# MyFly2.net
KiCad netlist of a schematic drawn in Altium Designer
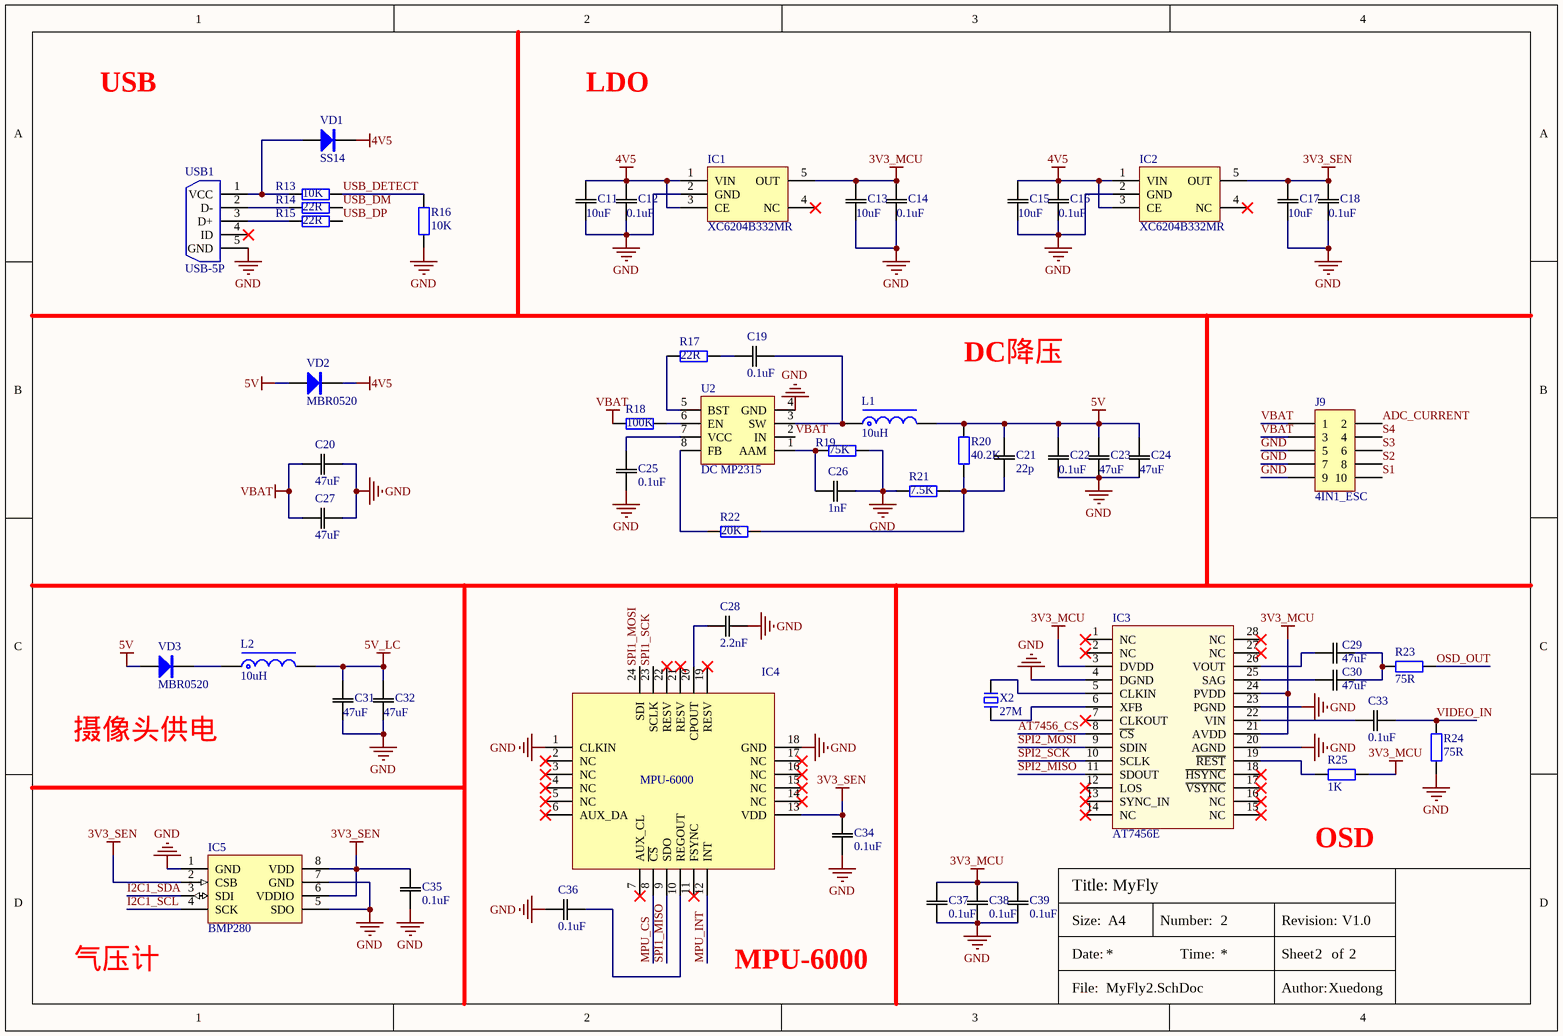
[diagram p0: MyFly2.SchDoc]

(export (version "E")
  (design (tool "Eeschema 10.0.6"))
  (components
    (comp (ref "C11")
      (value "10uF")
      (footprint "CAP_0603")
      (description "无极性贴片电容")
      (fields
        (field (name "MANUFACTURER_PART_NUMBER") "04023A0R3BAT2A")
        (field (name "COPYRIGHT") "Copyright (C) 2016 Accelerated Designs. All rights reserved")
      )
      (libsource (lib "mySchLib") (part "CAP"))
    )
    (comp (ref "C12")
      (value "0.1uF")
      (footprint "CAP_0603")
      (description "无极性贴片电容")
      (fields
        (field (name "MANUFACTURER_PART_NUMBER") "04023A0R3BAT2A")
        (field (name "COPYRIGHT") "Copyright (C) 2016 Accelerated Designs. All rights reserved")
      )
      (libsource (lib "mySchLib") (part "CAP"))
    )
    (comp (ref "C13")
      (value "10uF")
      (footprint "CAP_0603")
      (description "无极性贴片电容")
      (fields
        (field (name "MANUFACTURER_PART_NUMBER") "04023A0R3BAT2A")
        (field (name "COPYRIGHT") "Copyright (C) 2016 Accelerated Designs. All rights reserved")
      )
      (libsource (lib "mySchLib") (part "CAP"))
    )
    (comp (ref "C14")
      (value "0.1uF")
      (footprint "CAP_0603")
      (description "无极性贴片电容")
      (fields
        (field (name "MANUFACTURER_PART_NUMBER") "04023A0R3BAT2A")
        (field (name "COPYRIGHT") "Copyright (C) 2016 Accelerated Designs. All rights reserved")
      )
      (libsource (lib "mySchLib") (part "CAP"))
    )
    (comp (ref "C15")
      (value "10uF")
      (footprint "CAP_0603")
      (description "无极性贴片电容")
      (fields
        (field (name "MANUFACTURER_PART_NUMBER") "04023A0R3BAT2A")
        (field (name "COPYRIGHT") "Copyright (C) 2016 Accelerated Designs. All rights reserved")
      )
      (libsource (lib "mySchLib") (part "CAP"))
    )
    (comp (ref "C16")
      (value "0.1uF")
      (footprint "CAP_0603")
      (description "无极性贴片电容")
      (fields
        (field (name "MANUFACTURER_PART_NUMBER") "04023A0R3BAT2A")
        (field (name "COPYRIGHT") "Copyright (C) 2016 Accelerated Designs. All rights reserved")
      )
      (libsource (lib "mySchLib") (part "CAP"))
    )
    (comp (ref "C17")
      (value "10uF")
      (footprint "CAP_0603")
      (description "无极性贴片电容")
      (fields
        (field (name "MANUFACTURER_PART_NUMBER") "04023A0R3BAT2A")
        (field (name "COPYRIGHT") "Copyright (C) 2016 Accelerated Designs. All rights reserved")
      )
      (libsource (lib "mySchLib") (part "CAP"))
    )
    (comp (ref "C18")
      (value "0.1uF")
      (footprint "CAP_0603")
      (description "无极性贴片电容")
      (fields
        (field (name "MANUFACTURER_PART_NUMBER") "04023A0R3BAT2A")
        (field (name "COPYRIGHT") "Copyright (C) 2016 Accelerated Designs. All rights reserved")
      )
      (libsource (lib "mySchLib") (part "CAP"))
    )
    (comp (ref "C19")
      (value "0.1uF")
      (footprint "CAP_0603")
      (description "无极性贴片电容")
      (fields
        (field (name "MANUFACTURER_PART_NUMBER") "04023A0R3BAT2A")
        (field (name "COPYRIGHT") "Copyright (C) 2016 Accelerated Designs. All rights reserved")
      )
      (libsource (lib "mySchLib") (part "CAP"))
    )
    (comp (ref "C20")
      (value "47uF")
      (footprint "CAP_1206")
      (description "无极性贴片电容")
      (fields
        (field (name "MANUFACTURER_PART_NUMBER") "04023A0R3BAT2A")
        (field (name "COPYRIGHT") "Copyright (C) 2016 Accelerated Designs. All rights reserved")
      )
      (libsource (lib "mySchLib") (part "CAP"))
    )
    (comp (ref "C21")
      (value "22p")
      (footprint "CAP_0603")
      (description "无极性贴片电容")
      (fields
        (field (name "MANUFACTURER_PART_NUMBER") "04023A0R3BAT2A")
        (field (name "COPYRIGHT") "Copyright (C) 2016 Accelerated Designs. All rights reserved")
      )
      (libsource (lib "mySchLib") (part "CAP"))
    )
    (comp (ref "C22")
      (value "0.1uF")
      (footprint "CAP_0603")
      (description "无极性贴片电容")
      (fields
        (field (name "MANUFACTURER_PART_NUMBER") "04023A0R3BAT2A")
        (field (name "COPYRIGHT") "Copyright (C) 2016 Accelerated Designs. All rights reserved")
      )
      (libsource (lib "mySchLib") (part "CAP"))
    )
    (comp (ref "C23")
      (value "47uF")
      (footprint "CAP_1206")
      (description "无极性贴片电容")
      (fields
        (field (name "MANUFACTURER_PART_NUMBER") "04023A0R3BAT2A")
        (field (name "COPYRIGHT") "Copyright (C) 2016 Accelerated Designs. All rights reserved")
      )
      (libsource (lib "mySchLib") (part "CAP"))
    )
    (comp (ref "C24")
      (value "47uF")
      (footprint "CAP_1206")
      (description "无极性贴片电容")
      (fields
        (field (name "MANUFACTURER_PART_NUMBER") "04023A0R3BAT2A")
        (field (name "COPYRIGHT") "Copyright (C) 2016 Accelerated Designs. All rights reserved")
      )
      (libsource (lib "mySchLib") (part "CAP"))
    )
    (comp (ref "C25")
      (value "0.1uF")
      (footprint "CAP_0603")
      (description "无极性贴片电容")
      (fields
        (field (name "MANUFACTURER_PART_NUMBER") "04023A0R3BAT2A")
        (field (name "COPYRIGHT") "Copyright (C) 2016 Accelerated Designs. All rights reserved")
      )
      (libsource (lib "mySchLib") (part "CAP"))
    )
    (comp (ref "C26")
      (value "1nF")
      (footprint "CAP_0603")
      (description "无极性贴片电容")
      (fields
        (field (name "MANUFACTURER_PART_NUMBER") "04023A0R3BAT2A")
        (field (name "COPYRIGHT") "Copyright (C) 2016 Accelerated Designs. All rights reserved")
      )
      (libsource (lib "mySchLib") (part "CAP"))
    )
    (comp (ref "C27")
      (value "47uF")
      (footprint "CAP_1206")
      (description "无极性贴片电容")
      (fields
        (field (name "MANUFACTURER_PART_NUMBER") "04023A0R3BAT2A")
        (field (name "COPYRIGHT") "Copyright (C) 2016 Accelerated Designs. All rights reserved")
      )
      (libsource (lib "mySchLib") (part "CAP"))
    )
    (comp (ref "C28")
      (value "2.2nF")
      (footprint "CAP_0402")
      (description "无极性贴片电容")
      (fields
        (field (name "MANUFACTURER_PART_NUMBER") "04023A0R3BAT2A")
        (field (name "COPYRIGHT") "Copyright (C) 2016 Accelerated Designs. All rights reserved")
      )
      (libsource (lib "mySchLib") (part "CAP"))
    )
    (comp (ref "C29")
      (value "47uF")
      (footprint "CAP_0805")
      (description "无极性贴片电容")
      (fields
        (field (name "MANUFACTURER_PART_NUMBER") "04023A0R3BAT2A")
        (field (name "COPYRIGHT") "Copyright (C) 2016 Accelerated Designs. All rights reserved")
      )
      (libsource (lib "mySchLib") (part "CAP"))
    )
    (comp (ref "C30")
      (value "47uF")
      (footprint "CAP_0805")
      (description "无极性贴片电容")
      (fields
        (field (name "MANUFACTURER_PART_NUMBER") "04023A0R3BAT2A")
        (field (name "COPYRIGHT") "Copyright (C) 2016 Accelerated Designs. All rights reserved")
      )
      (libsource (lib "mySchLib") (part "CAP"))
    )
    (comp (ref "C31")
      (value "47uF")
      (footprint "CAP_0805")
      (description "无极性贴片电容")
      (fields
        (field (name "MANUFACTURER_PART_NUMBER") "04023A0R3BAT2A")
        (field (name "COPYRIGHT") "Copyright (C) 2016 Accelerated Designs. All rights reserved")
      )
      (libsource (lib "mySchLib") (part "CAP"))
    )
    (comp (ref "C32")
      (value "47uF")
      (footprint "CAP_0805")
      (description "无极性贴片电容")
      (fields
        (field (name "MANUFACTURER_PART_NUMBER") "04023A0R3BAT2A")
        (field (name "COPYRIGHT") "Copyright (C) 2016 Accelerated Designs. All rights reserved")
      )
      (libsource (lib "mySchLib") (part "CAP"))
    )
    (comp (ref "C33")
      (value "0.1uF")
      (footprint "CAP_0402")
      (description "无极性贴片电容")
      (fields
        (field (name "MANUFACTURER_PART_NUMBER") "04023A0R3BAT2A")
        (field (name "COPYRIGHT") "Copyright (C) 2016 Accelerated Designs. All rights reserved")
      )
      (libsource (lib "mySchLib") (part "CAP"))
    )
    (comp (ref "C34")
      (value "0.1uF")
      (footprint "CAP_0402")
      (description "无极性贴片电容")
      (fields
        (field (name "MANUFACTURER_PART_NUMBER") "04023A0R3BAT2A")
        (field (name "COPYRIGHT") "Copyright (C) 2016 Accelerated Designs. All rights reserved")
      )
      (libsource (lib "mySchLib") (part "CAP"))
    )
    (comp (ref "C35")
      (value "0.1uF")
      (footprint "CAP_0603")
      (description "无极性贴片电容")
      (fields
        (field (name "MANUFACTURER_PART_NUMBER") "04023A0R3BAT2A")
        (field (name "COPYRIGHT") "Copyright (C) 2016 Accelerated Designs. All rights reserved")
      )
      (libsource (lib "mySchLib") (part "CAP"))
    )
    (comp (ref "C36")
      (value "0.1uF")
      (footprint "CAP_0402")
      (description "无极性贴片电容")
      (fields
        (field (name "MANUFACTURER_PART_NUMBER") "04023A0R3BAT2A")
        (field (name "COPYRIGHT") "Copyright (C) 2016 Accelerated Designs. All rights reserved")
      )
      (libsource (lib "mySchLib") (part "CAP"))
    )
    (comp (ref "C37")
      (value "0.1uF")
      (footprint "CAP_0402")
      (description "无极性贴片电容")
      (fields
        (field (name "MANUFACTURER_PART_NUMBER") "04023A0R3BAT2A")
        (field (name "COPYRIGHT") "Copyright (C) 2016 Accelerated Designs. All rights reserved")
      )
      (libsource (lib "mySchLib") (part "CAP"))
    )
    (comp (ref "C38")
      (value "0.1uF")
      (footprint "CAP_0402")
      (description "无极性贴片电容")
      (fields
        (field (name "MANUFACTURER_PART_NUMBER") "04023A0R3BAT2A")
        (field (name "COPYRIGHT") "Copyright (C) 2016 Accelerated Designs. All rights reserved")
      )
      (libsource (lib "mySchLib") (part "CAP"))
    )
    (comp (ref "C39")
      (value "0.1uF")
      (footprint "CAP_0402")
      (description "无极性贴片电容")
      (fields
        (field (name "MANUFACTURER_PART_NUMBER") "04023A0R3BAT2A")
        (field (name "COPYRIGHT") "Copyright (C) 2016 Accelerated Designs. All rights reserved")
      )
      (libsource (lib "mySchLib") (part "CAP"))
    )
    (comp (ref "IC1")
      (value "XC6204B332MR")
      (footprint "SOT23-5L")
      (description "LDO")
      (fields (field (name "版权归属") "源创客"))
      (libsource (lib "mySchLib") (part "LDO XC6204"))
    )
    (comp (ref "IC2")
      (value "XC6204B332MR")
      (footprint "SOT23-5L")
      (description "LDO")
      (fields (field (name "版权归属") "源创客"))
      (libsource (lib "mySchLib") (part "LDO XC6204"))
    )
    (comp (ref "IC3")
      (value "AT7456E")
      (footprint "TSSOP28_L_E")
      (description "OSD芯片")
      (libsource (lib "mySchLib") (part "AT7456E"))
    )
    (comp (ref "IC4")
      (value "MPU-6000")
      (footprint "QFN24 4X4_N")
      (description "传感器")
      (libsource (lib "mySchLib") (part "MPU-6000"))
    )
    (comp (ref "IC5")
      (value "BMP280")
      (footprint "BMP280 LGA8")
      (description "气压传感器")
      (libsource (lib "mySchLib") (part "BMP280"))
    )
    (comp (ref "J9")
      (value "4IN1_ESC")
      (footprint "HDR1.27 2x5-SMD")
      (description "2x5P-接插件")
      (fields (field (name "MANUFACTURER_PART_NUMBER") "826656-5"))
      (libsource (lib "mySchLib") (part "Header_2x5"))
    )
    (comp (ref "L1")
      (value "10uH")
      (footprint "L-SMD-0420")
      (description "功率屏蔽电感")
      (fields (field (name "版权归属") "源创客"))
      (libsource (lib "mySchLib") (part "L-CDRH"))
    )
    (comp (ref "L2")
      (value "10uH")
      (footprint "NR3015")
      (description "NR功率电感")
      (fields (field (name "版权归属") "源创客"))
      (libsource (lib "mySchLib") (part "L-NR"))
    )
    (comp (ref "R13")
      (value "10K")
      (footprint "Res_0402")
      (description "贴片电阻")
      (fields (field (name "MANUFACTURER_PART_NUMBER") "RC0402FR-070RL"))
      (libsource (lib "mySchLib") (part "RES"))
    )
    (comp (ref "R14")
      (value "22R")
      (footprint "Res_0402")
      (description "贴片电阻")
      (fields (field (name "MANUFACTURER_PART_NUMBER") "RC0402FR-070RL"))
      (libsource (lib "mySchLib") (part "RES"))
    )
    (comp (ref "R15")
      (value "22R")
      (footprint "Res_0402")
      (description "贴片电阻")
      (fields (field (name "MANUFACTURER_PART_NUMBER") "RC0402FR-070RL"))
      (libsource (lib "mySchLib") (part "RES"))
    )
    (comp (ref "R16")
      (value "10K")
      (footprint "Res_0402")
      (description "贴片电阻")
      (fields (field (name "MANUFACTURER_PART_NUMBER") "RC0402FR-070RL"))
      (libsource (lib "mySchLib") (part "RES"))
    )
    (comp (ref "R17")
      (value "22R")
      (footprint "RES_0603")
      (description "贴片电阻")
      (fields (field (name "MANUFACTURER_PART_NUMBER") "RC0402FR-070RL"))
      (libsource (lib "mySchLib") (part "RES"))
    )
    (comp (ref "R18")
      (value "100K")
      (footprint "RES_0603")
      (description "贴片电阻")
      (fields (field (name "MANUFACTURER_PART_NUMBER") "RC0402FR-070RL"))
      (libsource (lib "mySchLib") (part "RES"))
    )
    (comp (ref "R19")
      (value "75K")
      (footprint "RES_0603")
      (description "贴片电阻")
      (fields (field (name "MANUFACTURER_PART_NUMBER") "RC0402FR-070RL"))
      (libsource (lib "mySchLib") (part "RES"))
    )
    (comp (ref "R20")
      (value "40.2K")
      (footprint "RES_0603")
      (description "贴片电阻")
      (fields (field (name "MANUFACTURER_PART_NUMBER") "RC0402FR-070RL"))
      (libsource (lib "mySchLib") (part "RES"))
    )
    (comp (ref "R21")
      (value "7.5K")
      (footprint "RES_0603")
      (description "贴片电阻")
      (fields (field (name "MANUFACTURER_PART_NUMBER") "RC0402FR-070RL"))
      (libsource (lib "mySchLib") (part "RES"))
    )
    (comp (ref "R22")
      (value "20K")
      (footprint "RES_0603")
      (description "贴片电阻")
      (fields (field (name "MANUFACTURER_PART_NUMBER") "RC0402FR-070RL"))
      (libsource (lib "mySchLib") (part "RES"))
    )
    (comp (ref "R23")
      (value "75R")
      (footprint "Res_0402")
      (description "贴片电阻")
      (fields (field (name "MANUFACTURER_PART_NUMBER") "RC0402FR-070RL"))
      (libsource (lib "mySchLib") (part "RES"))
    )
    (comp (ref "R24")
      (value "75R")
      (footprint "Res_0402")
      (description "贴片电阻")
      (fields (field (name "MANUFACTURER_PART_NUMBER") "RC0402FR-070RL"))
      (libsource (lib "mySchLib") (part "RES"))
    )
    (comp (ref "R25")
      (value "1K")
      (footprint "Res_0402")
      (description "贴片电阻")
      (fields (field (name "MANUFACTURER_PART_NUMBER") "RC0402FR-070RL"))
      (libsource (lib "mySchLib") (part "RES"))
    )
    (comp (ref "U2")
      (value "DC MP2315")
      (footprint "SOT23-8L")
      (description "DC降压芯片")
      (libsource (lib "mySchLib") (part "DC MP2315"))
    )
    (comp (ref "USB1")
      (value "USB-5P")
      (footprint "USB-MICRO_E")
      (description "微型USB母座")
      (fields (field (name "版权归属") "源创客"))
      (libsource (lib "mySchLib") (part "USB-5P"))
    )
    (comp (ref "VD1")
      (value "SS14")
      (footprint "SOD-123")
      (description "肖特基二极管")
      (fields (field (name "版权归属") "源创客"))
      (libsource (lib "mySchLib") (part "SS14"))
    )
    (comp (ref "VD2")
      (value "MBR0520")
      (footprint "SOD-123")
      (description "肖特基二极管")
      (fields (field (name "版权归属") "源创客"))
      (libsource (lib "mySchLib") (part "SS14"))
    )
    (comp (ref "VD3")
      (value "MBR0520")
      (footprint "SOD-123")
      (description "肖特基二极管")
      (fields (field (name "版权归属") "源创客"))
      (libsource (lib "mySchLib") (part "SS14"))
    )
    (comp (ref "X2")
      (value "27M")
      (footprint "XTAL-3225")
      (description "4脚无源晶振")
      (fields (field (name "版权归属") "源创客"))
      (libsource (lib "mySchLib") (part "XTAL-4P"))
    )
  )
  (nets
    (net (code "1") (name "/ADC_CURRENT") (class "Default")
      (node (ref "J9") (pin "2") (pinfunction "2_2") (pintype "passive"))
    )
    (net (code "2") (name "/AT7456_CS") (class "Default")
      (node (ref "IC3") (pin "8") (pinfunction "~{CS}_8") (pintype "passive"))
    )
    (net (code "3") (name "/I2C1_SCL") (class "Default")
      (node (ref "IC5") (pin "4") (pinfunction "SCK_4") (pintype "passive"))
    )
    (net (code "4") (name "/I2C1_SDA") (class "Default")
      (node (ref "IC5") (pin "3") (pinfunction "SDI_3") (pintype "bidirectional"))
    )
    (net (code "5") (name "/MPU_CS") (class "Default")
      (node (ref "IC4") (pin "8") (pinfunction "~{CS}_8") (pintype "passive"))
    )
    (net (code "6") (name "/MPU_INT") (class "Default")
      (node (ref "IC4") (pin "12") (pinfunction "INT_12") (pintype "passive"))
    )
    (net (code "7") (name "/OSD_OUT") (class "Default")
      (node (ref "R23") (pin "2") (pinfunction "2_2") (pintype "passive"))
    )
    (net (code "8") (name "/S1") (class "Default")
      (node (ref "J9") (pin "10") (pinfunction "10_10") (pintype "passive"))
    )
    (net (code "9") (name "/S2") (class "Default")
      (node (ref "J9") (pin "8") (pinfunction "8_8") (pintype "passive"))
    )
    (net (code "10") (name "/S3") (class "Default")
      (node (ref "J9") (pin "6") (pinfunction "6_6") (pintype "passive"))
    )
    (net (code "11") (name "/S4") (class "Default")
      (node (ref "J9") (pin "4") (pinfunction "4_4") (pintype "passive"))
    )
    (net (code "12") (name "/SPI1_MISO") (class "Default")
      (node (ref "IC4") (pin "9") (pinfunction "SDO_9") (pintype "passive"))
    )
    (net (code "13") (name "/SPI1_MOSI") (class "Default")
      (node (ref "IC4") (pin "24") (pinfunction "SDI_24") (pintype "passive"))
    )
    (net (code "14") (name "/SPI1_SCK") (class "Default")
      (node (ref "IC4") (pin "23") (pinfunction "SCLK_23") (pintype "passive"))
    )
    (net (code "15") (name "/SPI2_MISO") (class "Default")
      (node (ref "IC3") (pin "11") (pinfunction "SDOUT_11") (pintype "passive"))
    )
    (net (code "16") (name "/SPI2_MOSI") (class "Default")
      (node (ref "IC3") (pin "9") (pinfunction "SDIN_9") (pintype "passive"))
    )
    (net (code "17") (name "/SPI2_SCK") (class "Default")
      (node (ref "IC3") (pin "10") (pinfunction "SCLK_10") (pintype "passive"))
    )
    (net (code "18") (name "/USB_DETECT") (class "Default")
      (node (ref "R13") (pin "2") (pinfunction "2_2") (pintype "passive"))
      (node (ref "R16") (pin "2") (pinfunction "2_2") (pintype "passive"))
    )
    (net (code "19") (name "/USB_DM") (class "Default")
      (node (ref "R14") (pin "2") (pinfunction "2_2") (pintype "passive"))
    )
    (net (code "20") (name "/USB_DP") (class "Default")
      (node (ref "R15") (pin "2") (pinfunction "2_2") (pintype "passive"))
    )
    (net (code "21") (name "/VIDEO_IN") (class "Default")
      (node (ref "C33") (pin "2") (pinfunction "EPAD_2") (pintype "passive"))
      (node (ref "R24") (pin "2") (pinfunction "2_2") (pintype "passive"))
    )
    (net (code "22") (name "3V3_MCU") (class "Default")
      (node (ref "C13") (pin "2") (pinfunction "EPAD_2") (pintype "passive"))
      (node (ref "C14") (pin "2") (pinfunction "EPAD_2") (pintype "passive"))
      (node (ref "C37") (pin "2") (pinfunction "EPAD_2") (pintype "passive"))
      (node (ref "C38") (pin "2") (pinfunction "EPAD_2") (pintype "passive"))
      (node (ref "C39") (pin "2") (pinfunction "EPAD_2") (pintype "passive"))
      (node (ref "IC1") (pin "5") (pinfunction "OUT_5") (pintype "passive"))
      (node (ref "IC3") (pin "21") (pinfunction "AVDD_21") (pintype "passive"))
      (node (ref "IC3") (pin "24") (pinfunction "PVDD_24") (pintype "passive"))
      (node (ref "IC3") (pin "3") (pinfunction "DVDD_3") (pintype "passive"))
      (node (ref "R25") (pin "2") (pinfunction "2_2") (pintype "passive"))
    )
    (net (code "23") (name "3V3_SEN") (class "Default")
      (node (ref "C17") (pin "2") (pinfunction "EPAD_2") (pintype "passive"))
      (node (ref "C18") (pin "2") (pinfunction "EPAD_2") (pintype "passive"))
      (node (ref "C34") (pin "2") (pinfunction "EPAD_2") (pintype "passive"))
      (node (ref "C35") (pin "2") (pinfunction "EPAD_2") (pintype "passive"))
      (node (ref "IC2") (pin "5") (pinfunction "OUT_5") (pintype "passive"))
      (node (ref "IC4") (pin "13") (pinfunction "VDD_13") (pintype "passive"))
      (node (ref "IC5") (pin "2") (pinfunction "CSB_2") (pintype "input"))
      (node (ref "IC5") (pin "6") (pinfunction "VDDIO_6") (pintype "power_in"))
      (node (ref "IC5") (pin "8") (pinfunction "VDD_8") (pintype "power_in"))
    )
    (net (code "24") (name "4V5") (class "Default")
      (node (ref "C11") (pin "2") (pinfunction "EPAD_2") (pintype "passive"))
      (node (ref "C12") (pin "2") (pinfunction "EPAD_2") (pintype "passive"))
      (node (ref "C15") (pin "2") (pinfunction "EPAD_2") (pintype "passive"))
      (node (ref "C16") (pin "2") (pinfunction "EPAD_2") (pintype "passive"))
      (node (ref "IC1") (pin "1") (pinfunction "VIN_1") (pintype "passive"))
      (node (ref "IC1") (pin "3") (pinfunction "CE_3") (pintype "passive"))
      (node (ref "IC2") (pin "1") (pinfunction "VIN_1") (pintype "passive"))
      (node (ref "IC2") (pin "3") (pinfunction "CE_3") (pintype "passive"))
      (node (ref "VD1") (pin "2") (pinfunction "K_2") (pintype "passive"))
      (node (ref "VD2") (pin "2") (pinfunction "K_2") (pintype "passive"))
    )
    (net (code "25") (name "5V") (class "Default")
      (node (ref "C21") (pin "2") (pinfunction "EPAD_2") (pintype "passive"))
      (node (ref "C22") (pin "2") (pinfunction "EPAD_2") (pintype "passive"))
      (node (ref "C23") (pin "2") (pinfunction "EPAD_2") (pintype "passive"))
      (node (ref "C24") (pin "2") (pinfunction "EPAD_2") (pintype "passive"))
      (node (ref "L1") (pin "2") (pinfunction "2_2") (pintype "passive"))
      (node (ref "R20") (pin "2") (pinfunction "2_2") (pintype "passive"))
      (node (ref "VD2") (pin "1") (pinfunction "A_1") (pintype "passive"))
      (node (ref "VD3") (pin "1") (pinfunction "A_1") (pintype "passive"))
    )
    (net (code "26") (name "5V_LC") (class "Default")
      (node (ref "C31") (pin "2") (pinfunction "EPAD_2") (pintype "passive"))
      (node (ref "C32") (pin "2") (pinfunction "EPAD_2") (pintype "passive"))
      (node (ref "L2") (pin "2") (pinfunction "2_2") (pintype "passive"))
    )
    (net (code "27") (name "GND") (class "Default")
      (node (ref "C11") (pin "1") (pinfunction "EPAD_1") (pintype "passive"))
      (node (ref "C12") (pin "1") (pinfunction "EPAD_1") (pintype "passive"))
      (node (ref "C13") (pin "1") (pinfunction "EPAD_1") (pintype "passive"))
      (node (ref "C14") (pin "1") (pinfunction "EPAD_1") (pintype "passive"))
      (node (ref "C15") (pin "1") (pinfunction "EPAD_1") (pintype "passive"))
      (node (ref "C16") (pin "1") (pinfunction "EPAD_1") (pintype "passive"))
      (node (ref "C17") (pin "1") (pinfunction "EPAD_1") (pintype "passive"))
      (node (ref "C18") (pin "1") (pinfunction "EPAD_1") (pintype "passive"))
      (node (ref "C20") (pin "1") (pinfunction "EPAD_1") (pintype "passive"))
      (node (ref "C22") (pin "1") (pinfunction "EPAD_1") (pintype "passive"))
      (node (ref "C23") (pin "1") (pinfunction "EPAD_1") (pintype "passive"))
      (node (ref "C24") (pin "1") (pinfunction "EPAD_1") (pintype "passive"))
      (node (ref "C25") (pin "1") (pinfunction "EPAD_1") (pintype "passive"))
      (node (ref "C26") (pin "2") (pinfunction "EPAD_2") (pintype "passive"))
      (node (ref "C27") (pin "1") (pinfunction "EPAD_1") (pintype "passive"))
      (node (ref "C28") (pin "2") (pinfunction "EPAD_2") (pintype "passive"))
      (node (ref "C31") (pin "1") (pinfunction "EPAD_1") (pintype "passive"))
      (node (ref "C32") (pin "1") (pinfunction "EPAD_1") (pintype "passive"))
      (node (ref "C34") (pin "1") (pinfunction "EPAD_1") (pintype "passive"))
      (node (ref "C35") (pin "1") (pinfunction "EPAD_1") (pintype "passive"))
      (node (ref "C36") (pin "1") (pinfunction "EPAD_1") (pintype "passive"))
      (node (ref "C37") (pin "1") (pinfunction "EPAD_1") (pintype "passive"))
      (node (ref "C38") (pin "1") (pinfunction "EPAD_1") (pintype "passive"))
      (node (ref "C39") (pin "1") (pinfunction "EPAD_1") (pintype "passive"))
      (node (ref "IC1") (pin "2") (pinfunction "GND_2") (pintype "passive"))
      (node (ref "IC2") (pin "2") (pinfunction "GND_2") (pintype "passive"))
      (node (ref "IC3") (pin "20") (pinfunction "AGND_20") (pintype "passive"))
      (node (ref "IC3") (pin "23") (pinfunction "PGND_23") (pintype "passive"))
      (node (ref "IC3") (pin "4") (pinfunction "DGND_4") (pintype "passive"))
      (node (ref "IC4") (pin "1") (pinfunction "CLKIN_1") (pintype "passive"))
      (node (ref "IC4") (pin "18") (pinfunction "GND_18") (pintype "passive"))
      (node (ref "IC5") (pin "1") (pinfunction "GND_1") (pintype "passive"))
      (node (ref "IC5") (pin "5") (pinfunction "SDO_5") (pintype "passive"))
      (node (ref "IC5") (pin "7") (pinfunction "GND_7") (pintype "power_in"))
      (node (ref "J9") (pin "5") (pinfunction "5_5") (pintype "passive"))
      (node (ref "J9") (pin "7") (pinfunction "7_7") (pintype "passive"))
      (node (ref "J9") (pin "9") (pinfunction "9_9") (pintype "passive"))
      (node (ref "R16") (pin "1") (pinfunction "1_1") (pintype "passive"))
      (node (ref "R19") (pin "2") (pinfunction "2_2") (pintype "passive"))
      (node (ref "R21") (pin "1") (pinfunction "1_1") (pintype "passive"))
      (node (ref "R24") (pin "1") (pinfunction "1_1") (pintype "passive"))
      (node (ref "U2") (pin "4") (pinfunction "GND_4") (pintype "passive"))
      (node (ref "USB1") (pin "5") (pinfunction "GND_5") (pintype "passive"))
    )
    (net (code "28") (name "Net-(C19-EPAD-Pad1)") (class "Default")
      (node (ref "C19") (pin "1") (pinfunction "EPAD_1") (pintype "passive"))
      (node (ref "R17") (pin "2") (pinfunction "2_2") (pintype "passive"))
    )
    (net (code "29") (name "Net-(C21-EPAD-Pad1)") (class "Default")
      (node (ref "C21") (pin "1") (pinfunction "EPAD_1") (pintype "passive"))
      (node (ref "R20") (pin "1") (pinfunction "1_1") (pintype "passive"))
      (node (ref "R21") (pin "2") (pinfunction "2_2") (pintype "passive"))
      (node (ref "R22") (pin "2") (pinfunction "2_2") (pintype "passive"))
    )
    (net (code "30") (name "Net-(C29-EPAD-Pad2)") (class "Default")
      (node (ref "C29") (pin "2") (pinfunction "EPAD_2") (pintype "passive"))
      (node (ref "C30") (pin "2") (pinfunction "EPAD_2") (pintype "passive"))
      (node (ref "R23") (pin "1") (pinfunction "1_1") (pintype "passive"))
    )
    (net (code "31") (name "Net-(IC3-CLKIN)") (class "Default")
      (node (ref "IC3") (pin "5") (pinfunction "CLKIN_5") (pintype "passive"))
      (node (ref "X2") (pin "3") (pinfunction "3_3") (pintype "passive"))
    )
    (net (code "32") (name "Net-(IC3-SAG)") (class "Default")
      (node (ref "C30") (pin "1") (pinfunction "EPAD_1") (pintype "passive"))
      (node (ref "IC3") (pin "25") (pinfunction "SAG_25") (pintype "passive"))
    )
    (net (code "33") (name "Net-(IC3-VIN)") (class "Default")
      (node (ref "C33") (pin "1") (pinfunction "EPAD_1") (pintype "passive"))
      (node (ref "IC3") (pin "22") (pinfunction "VIN_22") (pintype "passive"))
    )
    (net (code "34") (name "Net-(IC3-VOUT)") (class "Default")
      (node (ref "C29") (pin "1") (pinfunction "EPAD_1") (pintype "passive"))
      (node (ref "IC3") (pin "26") (pinfunction "VOUT_26") (pintype "passive"))
    )
    (net (code "35") (name "Net-(IC3-XFB)") (class "Default")
      (node (ref "IC3") (pin "6") (pinfunction "XFB_6") (pintype "passive"))
      (node (ref "X2") (pin "1") (pinfunction "1_1") (pintype "passive"))
    )
    (net (code "36") (name "Net-(IC3-~{REST})") (class "Default")
      (node (ref "IC3") (pin "19") (pinfunction "~{REST}_19") (pintype "passive"))
      (node (ref "R25") (pin "1") (pinfunction "1_1") (pintype "passive"))
    )
    (net (code "37") (name "Net-(IC4-CPOUT)") (class "Default")
      (node (ref "C28") (pin "1") (pinfunction "EPAD_1") (pintype "passive"))
      (node (ref "IC4") (pin "20") (pinfunction "CPOUT_20") (pintype "passive"))
    )
    (net (code "38") (name "Net-(IC4-REGOUT)") (class "Default")
      (node (ref "C36") (pin "2") (pinfunction "EPAD_2") (pintype "passive"))
      (node (ref "IC4") (pin "10") (pinfunction "REGOUT_10") (pintype "passive"))
    )
    (net (code "39") (name "Net-(U2-AAM)") (class "Default")
      (node (ref "C26") (pin "1") (pinfunction "EPAD_1") (pintype "passive"))
      (node (ref "R19") (pin "1") (pinfunction "1_1") (pintype "passive"))
      (node (ref "U2") (pin "1") (pinfunction "AAM_1") (pintype "passive"))
    )
    (net (code "40") (name "Net-(U2-BST)") (class "Default")
      (node (ref "R17") (pin "1") (pinfunction "1_1") (pintype "passive"))
      (node (ref "U2") (pin "5") (pinfunction "BST_5") (pintype "passive"))
    )
    (net (code "41") (name "Net-(U2-EN)") (class "Default")
      (node (ref "R18") (pin "2") (pinfunction "2_2") (pintype "passive"))
      (node (ref "U2") (pin "6") (pinfunction "EN_6") (pintype "passive"))
    )
    (net (code "42") (name "Net-(U2-FB)") (class "Default")
      (node (ref "R22") (pin "1") (pinfunction "1_1") (pintype "passive"))
      (node (ref "U2") (pin "8") (pinfunction "FB_8") (pintype "passive"))
    )
    (net (code "43") (name "Net-(U2-SW)") (class "Default")
      (node (ref "C19") (pin "2") (pinfunction "EPAD_2") (pintype "passive"))
      (node (ref "L1") (pin "1") (pinfunction "1_1") (pintype "passive"))
      (node (ref "U2") (pin "3") (pinfunction "SW_3") (pintype "passive"))
    )
    (net (code "44") (name "Net-(U2-VCC)") (class "Default")
      (node (ref "C25") (pin "2") (pinfunction "EPAD_2") (pintype "passive"))
      (node (ref "U2") (pin "7") (pinfunction "VCC_7") (pintype "passive"))
    )
    (net (code "45") (name "Net-(USB1-D+)") (class "Default")
      (node (ref "R15") (pin "1") (pinfunction "1_1") (pintype "passive"))
      (node (ref "USB1") (pin "3") (pinfunction "D+_3") (pintype "passive"))
    )
    (net (code "46") (name "Net-(USB1-D-)") (class "Default")
      (node (ref "R14") (pin "1") (pinfunction "1_1") (pintype "passive"))
      (node (ref "USB1") (pin "2") (pinfunction "D-_2") (pintype "passive"))
    )
    (net (code "47") (name "Net-(USB1-VCC)") (class "Default")
      (node (ref "R13") (pin "1") (pinfunction "1_1") (pintype "passive"))
      (node (ref "USB1") (pin "1") (pinfunction "VCC_1") (pintype "passive"))
      (node (ref "VD1") (pin "1") (pinfunction "A_1") (pintype "passive"))
    )
    (net (code "48") (name "Net-(VD3-K)") (class "Default")
      (node (ref "L2") (pin "1") (pinfunction "1_1") (pintype "passive"))
      (node (ref "VD3") (pin "2") (pinfunction "K_2") (pintype "passive"))
    )
    (net (code "49") (name "VBAT") (class "Default")
      (node (ref "C20") (pin "2") (pinfunction "EPAD_2") (pintype "passive"))
      (node (ref "C27") (pin "2") (pinfunction "EPAD_2") (pintype "passive"))
      (node (ref "J9") (pin "1") (pinfunction "1_1") (pintype "passive"))
      (node (ref "J9") (pin "3") (pinfunction "3_3") (pintype "passive"))
      (node (ref "R18") (pin "1") (pinfunction "1_1") (pintype "passive"))
      (node (ref "U2") (pin "2") (pinfunction "IN_2") (pintype "passive"))
    )
    (net (code "50") (name "unconnected-(IC1-NC-Pad4)") (class "Default")
      (node (ref "IC1") (pin "4") (pinfunction "NC_4") (pintype "passive+no_connect"))
    )
    (net (code "51") (name "unconnected-(IC2-NC-Pad4)") (class "Default")
      (node (ref "IC2") (pin "4") (pinfunction "NC_4") (pintype "passive+no_connect"))
    )
    (net (code "52") (name "unconnected-(IC3-CLKOUT-Pad7)") (class "Default")
      (node (ref "IC3") (pin "7") (pinfunction "CLKOUT_7") (pintype "passive+no_connect"))
    )
    (net (code "53") (name "unconnected-(IC3-LOS-Pad12)") (class "Default")
      (node (ref "IC3") (pin "12") (pinfunction "LOS_12") (pintype "passive+no_connect"))
    )
    (net (code "54") (name "unconnected-(IC3-NC-Pad1)") (class "Default")
      (node (ref "IC3") (pin "1") (pinfunction "NC_1") (pintype "passive+no_connect"))
    )
    (net (code "55") (name "unconnected-(IC3-NC-Pad2)") (class "Default")
      (node (ref "IC3") (pin "2") (pinfunction "NC_2") (pintype "passive+no_connect"))
    )
    (net (code "56") (name "unconnected-(IC3-NC-Pad14)") (class "Default")
      (node (ref "IC3") (pin "14") (pinfunction "NC_14") (pintype "passive+no_connect"))
    )
    (net (code "57") (name "unconnected-(IC3-NC-Pad15)") (class "Default")
      (node (ref "IC3") (pin "15") (pinfunction "NC_15") (pintype "passive+no_connect"))
    )
    (net (code "58") (name "unconnected-(IC3-NC-Pad16)") (class "Default")
      (node (ref "IC3") (pin "16") (pinfunction "NC_16") (pintype "passive+no_connect"))
    )
    (net (code "59") (name "unconnected-(IC3-NC-Pad27)") (class "Default")
      (node (ref "IC3") (pin "27") (pinfunction "NC_27") (pintype "passive+no_connect"))
    )
    (net (code "60") (name "unconnected-(IC3-NC-Pad28)") (class "Default")
      (node (ref "IC3") (pin "28") (pinfunction "NC_28") (pintype "passive+no_connect"))
    )
    (net (code "61") (name "unconnected-(IC3-SYNC_IN-Pad13)") (class "Default")
      (node (ref "IC3") (pin "13") (pinfunction "SYNC_IN_13") (pintype "passive+no_connect"))
    )
    (net (code "62") (name "unconnected-(IC3-~{HSYNC}-Pad18)") (class "Default")
      (node (ref "IC3") (pin "18") (pinfunction "~{HSYNC}_18") (pintype "passive+no_connect"))
    )
    (net (code "63") (name "unconnected-(IC3-~{VSYNC}-Pad17)") (class "Default")
      (node (ref "IC3") (pin "17") (pinfunction "~{VSYNC}_17") (pintype "passive+no_connect"))
    )
    (net (code "64") (name "unconnected-(IC4-AUX_CL-Pad7)") (class "Default")
      (node (ref "IC4") (pin "7") (pinfunction "AUX_CL_7") (pintype "passive+no_connect"))
    )
    (net (code "65") (name "unconnected-(IC4-AUX_DA-Pad6)") (class "Default")
      (node (ref "IC4") (pin "6") (pinfunction "AUX_DA_6") (pintype "passive+no_connect"))
    )
    (net (code "66") (name "unconnected-(IC4-FSYNC-Pad11)") (class "Default")
      (node (ref "IC4") (pin "11") (pinfunction "FSYNC_11") (pintype "passive+no_connect"))
    )
    (net (code "67") (name "unconnected-(IC4-NC-Pad2)") (class "Default")
      (node (ref "IC4") (pin "2") (pinfunction "NC_2") (pintype "passive+no_connect"))
    )
    (net (code "68") (name "unconnected-(IC4-NC-Pad3)") (class "Default")
      (node (ref "IC4") (pin "3") (pinfunction "NC_3") (pintype "passive+no_connect"))
    )
    (net (code "69") (name "unconnected-(IC4-NC-Pad4)") (class "Default")
      (node (ref "IC4") (pin "4") (pinfunction "NC_4") (pintype "passive+no_connect"))
    )
    (net (code "70") (name "unconnected-(IC4-NC-Pad5)") (class "Default")
      (node (ref "IC4") (pin "5") (pinfunction "NC_5") (pintype "passive+no_connect"))
    )
    (net (code "71") (name "unconnected-(IC4-NC-Pad14)") (class "Default")
      (node (ref "IC4") (pin "14") (pinfunction "NC_14") (pintype "passive+no_connect"))
    )
    (net (code "72") (name "unconnected-(IC4-NC-Pad15)") (class "Default")
      (node (ref "IC4") (pin "15") (pinfunction "NC_15") (pintype "passive+no_connect"))
    )
    (net (code "73") (name "unconnected-(IC4-NC-Pad16)") (class "Default")
      (node (ref "IC4") (pin "16") (pinfunction "NC_16") (pintype "passive+no_connect"))
    )
    (net (code "74") (name "unconnected-(IC4-NC-Pad17)") (class "Default")
      (node (ref "IC4") (pin "17") (pinfunction "NC_17") (pintype "passive+no_connect"))
    )
    (net (code "75") (name "unconnected-(IC4-RESV-Pad19)") (class "Default")
      (node (ref "IC4") (pin "19") (pinfunction "RESV_19") (pintype "passive+no_connect"))
    )
    (net (code "76") (name "unconnected-(IC4-RESV-Pad21)") (class "Default")
      (node (ref "IC4") (pin "21") (pinfunction "RESV_21") (pintype "passive+no_connect"))
    )
    (net (code "77") (name "unconnected-(IC4-RESV-Pad22)") (class "Default")
      (node (ref "IC4") (pin "22") (pinfunction "RESV_22") (pintype "passive+no_connect"))
    )
    (net (code "78") (name "unconnected-(USB1-ID-Pad4)") (class "Default")
      (node (ref "USB1") (pin "4") (pinfunction "ID_4") (pintype "passive+no_connect"))
    )
  )
)
